# BallDetector6A.net
KiCad netlist of a schematic drawn in EAGLE
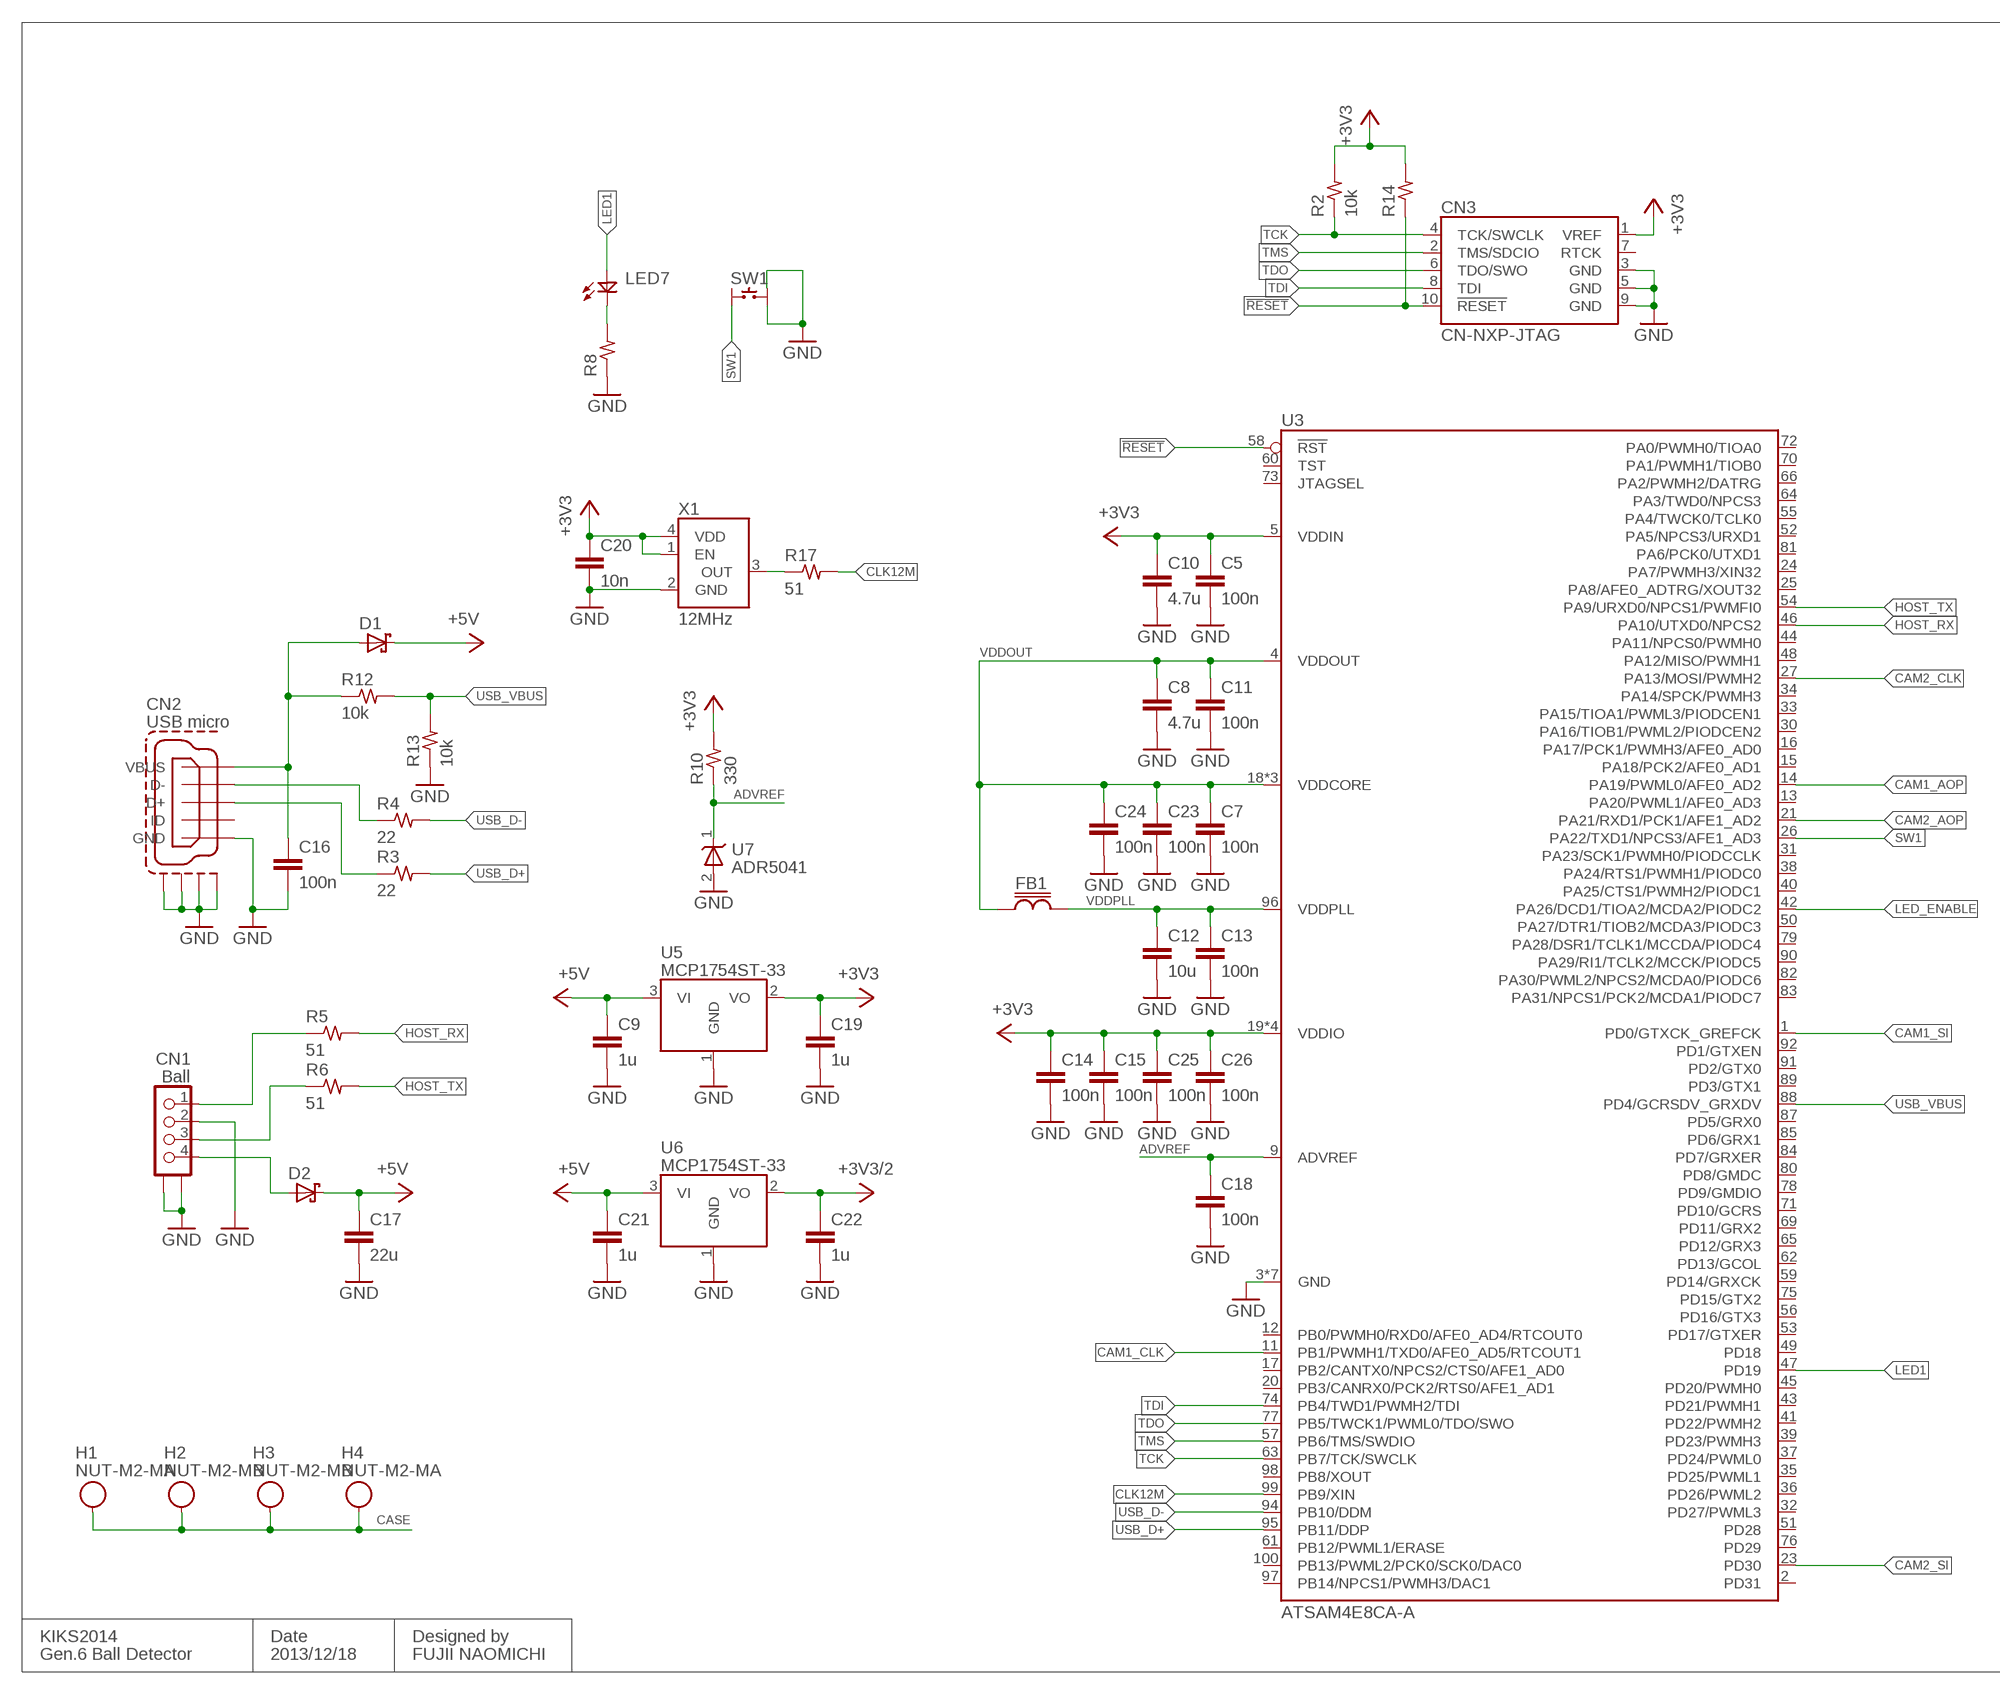
[diagram p0: schematic, sheet 1, part 1 of 2]
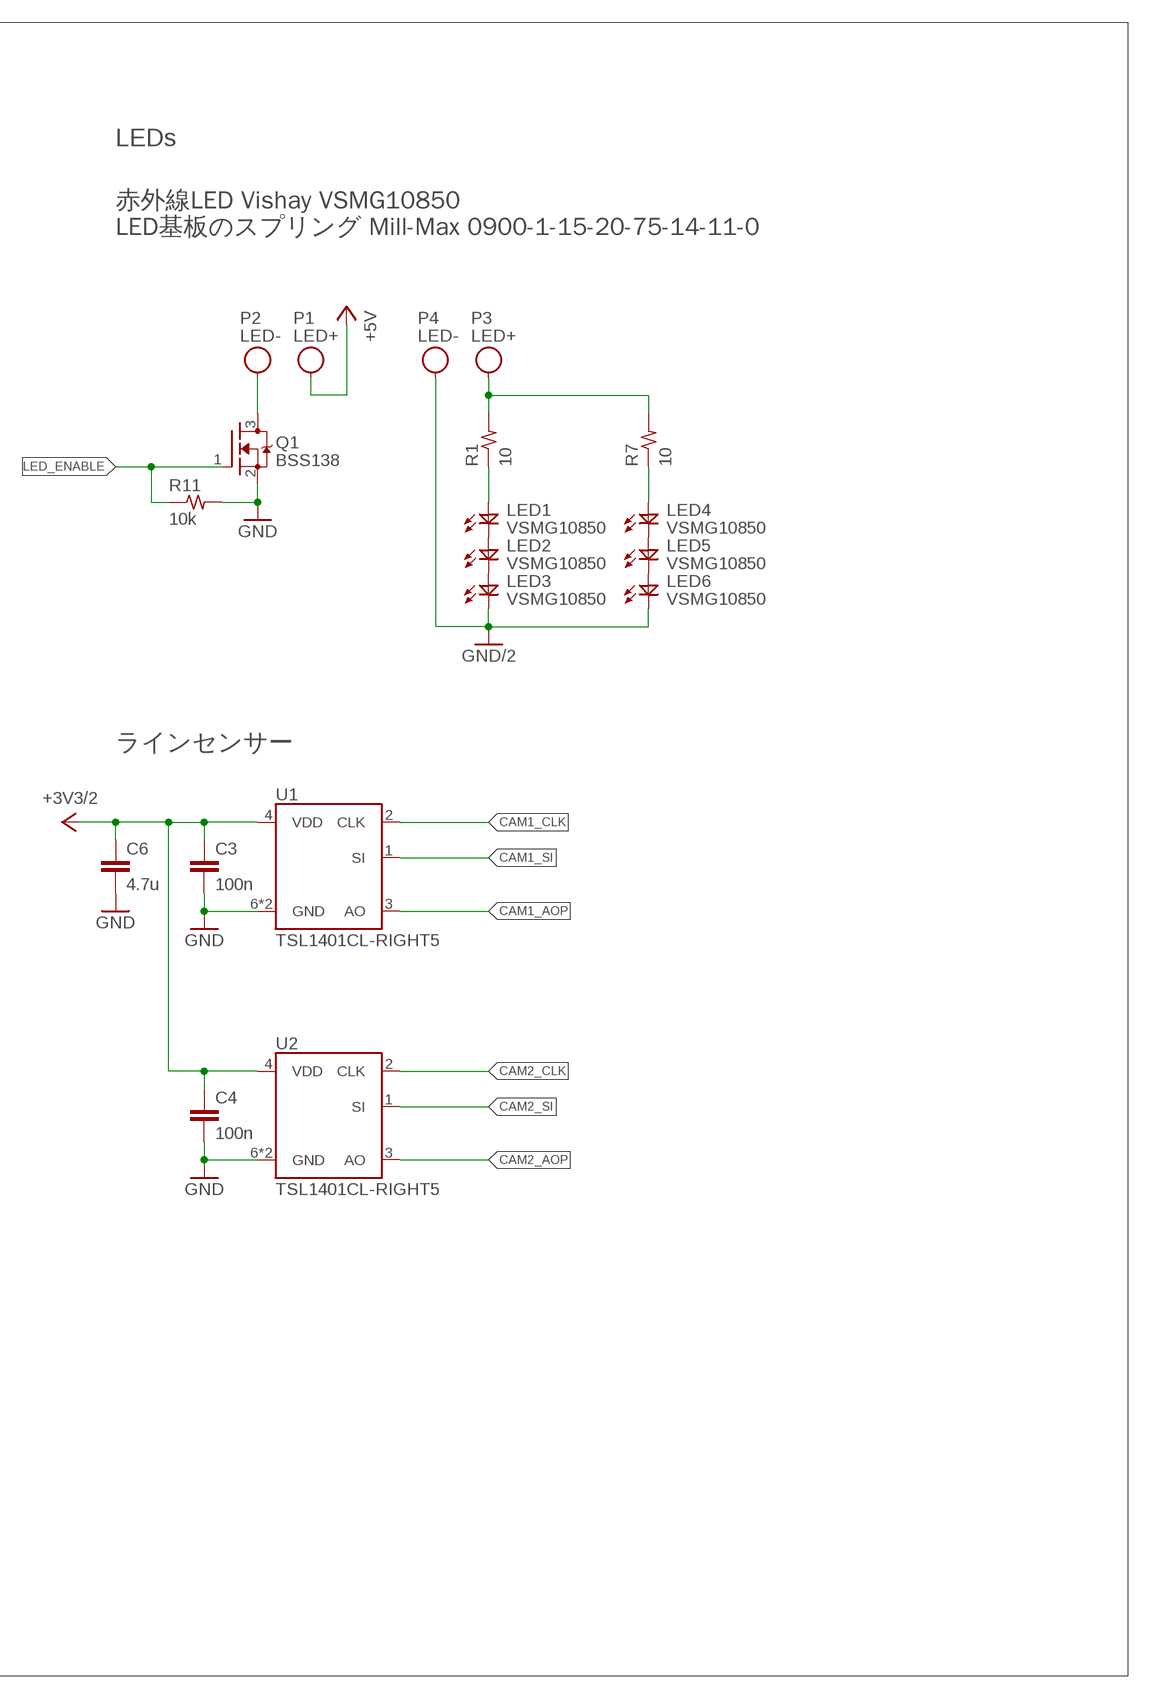
[diagram p1: schematic, sheet 1, part 2 of 2]

(export (version "E")
  (design (tool "Eeschema 10.0.6"))
  (components
    (comp (ref "C3")
      (value "100n")
      (footprint "eagle-import:1005")
      (libsource (lib "eagle-import") (part "C1005"))
    )
    (comp (ref "C4")
      (value "100n")
      (footprint "eagle-import:1005")
      (libsource (lib "eagle-import") (part "C1005"))
    )
    (comp (ref "C5")
      (value "100n")
      (footprint "eagle-import:1005")
      (libsource (lib "eagle-import") (part "C1005"))
    )
    (comp (ref "C6")
      (value "4.7u")
      (footprint "eagle-import:1608")
      (libsource (lib "eagle-import") (part "C1608"))
    )
    (comp (ref "C7")
      (value "100n")
      (footprint "eagle-import:1005")
      (libsource (lib "eagle-import") (part "C1005"))
    )
    (comp (ref "C8")
      (value "4.7u")
      (footprint "eagle-import:1608")
      (libsource (lib "eagle-import") (part "C1608"))
    )
    (comp (ref "C9")
      (value "1u")
      (footprint "eagle-import:1005")
      (libsource (lib "eagle-import") (part "C1005"))
    )
    (comp (ref "C10")
      (value "4.7u")
      (footprint "eagle-import:1608")
      (libsource (lib "eagle-import") (part "C1608"))
    )
    (comp (ref "C11")
      (value "100n")
      (footprint "eagle-import:1005")
      (libsource (lib "eagle-import") (part "C1005"))
    )
    (comp (ref "C12")
      (value "10u")
      (footprint "eagle-import:1005")
      (libsource (lib "eagle-import") (part "C1005"))
    )
    (comp (ref "C13")
      (value "100n")
      (footprint "eagle-import:1005")
      (libsource (lib "eagle-import") (part "C1005"))
    )
    (comp (ref "C14")
      (value "100n")
      (footprint "eagle-import:1005")
      (libsource (lib "eagle-import") (part "C1005"))
    )
    (comp (ref "C15")
      (value "100n")
      (footprint "eagle-import:1005")
      (libsource (lib "eagle-import") (part "C1005"))
    )
    (comp (ref "C16")
      (value "100n")
      (footprint "eagle-import:1005")
      (libsource (lib "eagle-import") (part "C1005"))
    )
    (comp (ref "C17")
      (value "22u")
      (footprint "eagle-import:2012")
      (libsource (lib "eagle-import") (part "C2012"))
    )
    (comp (ref "C18")
      (value "100n")
      (footprint "eagle-import:1005")
      (libsource (lib "eagle-import") (part "C1005"))
    )
    (comp (ref "C19")
      (value "1u")
      (footprint "eagle-import:1005")
      (libsource (lib "eagle-import") (part "C1005"))
    )
    (comp (ref "C20")
      (value "10n")
      (footprint "eagle-import:1005")
      (libsource (lib "eagle-import") (part "C1005"))
    )
    (comp (ref "C21")
      (value "1u")
      (footprint "eagle-import:1005")
      (libsource (lib "eagle-import") (part "C1005"))
    )
    (comp (ref "C22")
      (value "1u")
      (footprint "eagle-import:1005")
      (libsource (lib "eagle-import") (part "C1005"))
    )
    (comp (ref "C23")
      (value "100n")
      (footprint "eagle-import:1005")
      (libsource (lib "eagle-import") (part "C1005"))
    )
    (comp (ref "C24")
      (value "100n")
      (footprint "eagle-import:1005")
      (libsource (lib "eagle-import") (part "C1005"))
    )
    (comp (ref "C25")
      (value "100n")
      (footprint "eagle-import:1005")
      (libsource (lib "eagle-import") (part "C1005"))
    )
    (comp (ref "C26")
      (value "100n")
      (footprint "eagle-import:1005")
      (libsource (lib "eagle-import") (part "C1005"))
    )
    (comp (ref "CN1")
      (value "Ball")
      (footprint "eagle-import:53398-04")
      (libsource (lib "eagle-import") (part "53398-0471"))
    )
    (comp (ref "CN2")
      (value "USB micro")
      (footprint "eagle-import:ZX62-B-5PA")
      (libsource (lib "eagle-import") (part "ZX62-B-5PA"))
    )
    (comp (ref "CN3")
      (value "CN-NXP-JTAG")
      (footprint "eagle-import:PIN2X5-SMT1.27")
      (libsource (lib "eagle-import") (part "CN-NXP-JTAG"))
    )
    (comp (ref "D1")
      (value "SBD-SOD523")
      (footprint "eagle-import:SOD523")
      (libsource (lib "eagle-import") (part "SBD-SOD523"))
    )
    (comp (ref "D2")
      (value "SBD-SOD523")
      (footprint "eagle-import:SOD523")
      (libsource (lib "eagle-import") (part "SBD-SOD523"))
    )
    (comp (ref "FB1")
      (value "FB1608")
      (footprint "eagle-import:1608")
      (libsource (lib "eagle-import") (part "FB1608"))
    )
    (comp (ref "H1")
      (value "NUT-M2-MA")
      (footprint "eagle-import:NUT-M2-MA")
      (libsource (lib "eagle-import") (part "NUT-M2-MA"))
    )
    (comp (ref "H2")
      (value "NUT-M2-MB")
      (footprint "eagle-import:NUT-M2-MB")
      (libsource (lib "eagle-import") (part "NUT-M2-MB"))
    )
    (comp (ref "H3")
      (value "NUT-M2-MB")
      (footprint "eagle-import:NUT-M2-MB")
      (libsource (lib "eagle-import") (part "NUT-M2-MB"))
    )
    (comp (ref "H4")
      (value "NUT-M2-MA")
      (footprint "eagle-import:NUT-M2-MA")
      (libsource (lib "eagle-import") (part "NUT-M2-MA"))
    )
    (comp (ref "LED1")
      (value "VSMG10850")
      (footprint "eagle-import:3010")
      (libsource (lib "eagle-import") (part "VSMG10850"))
    )
    (comp (ref "LED2")
      (value "VSMG10850")
      (footprint "eagle-import:3010")
      (libsource (lib "eagle-import") (part "VSMG10850"))
    )
    (comp (ref "LED3")
      (value "VSMG10850")
      (footprint "eagle-import:3010")
      (libsource (lib "eagle-import") (part "VSMG10850"))
    )
    (comp (ref "LED4")
      (value "VSMG10850")
      (footprint "eagle-import:3010")
      (libsource (lib "eagle-import") (part "VSMG10850"))
    )
    (comp (ref "LED5")
      (value "VSMG10850")
      (footprint "eagle-import:3010")
      (libsource (lib "eagle-import") (part "VSMG10850"))
    )
    (comp (ref "LED6")
      (value "VSMG10850")
      (footprint "eagle-import:3010")
      (libsource (lib "eagle-import") (part "VSMG10850"))
    )
    (comp (ref "LED7")
      (value "LED1608")
      (footprint "eagle-import:1608")
      (libsource (lib "eagle-import") (part "LED1608"))
    )
    (comp (ref "P1")
      (value "LED+")
      (footprint "eagle-import:SPRING-72MIL")
      (libsource (lib "eagle-import") (part "SPRING-72MIL"))
    )
    (comp (ref "P2")
      (value "LED-")
      (footprint "eagle-import:SPRING-72MIL")
      (libsource (lib "eagle-import") (part "SPRING-72MIL"))
    )
    (comp (ref "P3")
      (value "LED+")
      (footprint "eagle-import:SPRING-72MIL")
      (libsource (lib "eagle-import") (part "SPRING-72MIL"))
    )
    (comp (ref "P4")
      (value "LED-")
      (footprint "eagle-import:SPRING-72MIL")
      (libsource (lib "eagle-import") (part "SPRING-72MIL"))
    )
    (comp (ref "Q1")
      (value "BSS138")
      (footprint "eagle-import:SOT23-3")
      (libsource (lib "eagle-import") (part "MOS-N-SOT23"))
    )
    (comp (ref "R1")
      (value "10")
      (footprint "eagle-import:1608")
      (libsource (lib "eagle-import") (part "R1608"))
    )
    (comp (ref "R2")
      (value "10k")
      (footprint "eagle-import:1005")
      (libsource (lib "eagle-import") (part "R1005"))
    )
    (comp (ref "R3")
      (value "22")
      (footprint "eagle-import:1005")
      (libsource (lib "eagle-import") (part "R1005"))
    )
    (comp (ref "R4")
      (value "22")
      (footprint "eagle-import:1005")
      (libsource (lib "eagle-import") (part "R1005"))
    )
    (comp (ref "R5")
      (value "51")
      (footprint "eagle-import:1005")
      (libsource (lib "eagle-import") (part "R1005"))
    )
    (comp (ref "R6")
      (value "51")
      (footprint "eagle-import:1005")
      (libsource (lib "eagle-import") (part "R1005"))
    )
    (comp (ref "R7")
      (value "10")
      (footprint "eagle-import:1608")
      (libsource (lib "eagle-import") (part "R1608"))
    )
    (comp (ref "R8")
      (value "R1005")
      (footprint "eagle-import:1005")
      (libsource (lib "eagle-import") (part "R1005"))
    )
    (comp (ref "R10")
      (value "330")
      (footprint "eagle-import:1005")
      (libsource (lib "eagle-import") (part "R1005"))
    )
    (comp (ref "R11")
      (value "10k")
      (footprint "eagle-import:1005")
      (libsource (lib "eagle-import") (part "R1005"))
    )
    (comp (ref "R12")
      (value "10k")
      (footprint "eagle-import:1005")
      (libsource (lib "eagle-import") (part "R1005"))
    )
    (comp (ref "R13")
      (value "10k")
      (footprint "eagle-import:1005")
      (libsource (lib "eagle-import") (part "R1005"))
    )
    (comp (ref "R14")
      (value "R1005")
      (footprint "eagle-import:1005")
      (libsource (lib "eagle-import") (part "R1005"))
    )
    (comp (ref "R17")
      (value "51")
      (footprint "eagle-import:1005")
      (libsource (lib "eagle-import") (part "R1005"))
    )
    (comp (ref "SW1")
      (value "SKRP")
      (footprint "eagle-import:SKRP")
      (libsource (lib "eagle-import") (part "SKRP"))
    )
    (comp (ref "U1")
      (value "TSL1401CL-RIGHT5")
      (footprint "eagle-import:TSL1401CL-RIGHT5")
      (libsource (lib "eagle-import") (part "TSL1401CL-RIGHT5"))
    )
    (comp (ref "U2")
      (value "TSL1401CL-RIGHT5")
      (footprint "eagle-import:TSL1401CL-RIGHT5")
      (libsource (lib "eagle-import") (part "TSL1401CL-RIGHT5"))
    )
    (comp (ref "U3")
      (value "ATSAM4E8CA-A")
      (footprint "eagle-import:QFP100-0.5")
      (libsource (lib "eagle-import") (part "ATSAM4ECA-?A8"))
    )
    (comp (ref "U5")
      (value "MCP1754ST-33")
      (footprint "eagle-import:SOT23-3")
      (libsource (lib "eagle-import") (part "MCP1754ST-33"))
    )
    (comp (ref "U6")
      (value "MCP1754ST-33")
      (footprint "eagle-import:SOT23-3")
      (libsource (lib "eagle-import") (part "MCP1754ST-33"))
    )
    (comp (ref "U7")
      (value "ADR5041")
      (footprint "eagle-import:SC70-3")
      (libsource (lib "eagle-import") (part "ADR5041"))
    )
    (comp (ref "X1")
      (value "12MHz")
      (footprint "eagle-import:OSC2520")
      (libsource (lib "eagle-import") (part "ASDMB"))
    )
  )
  (nets
    (net (code "1") (name "+3V3") (class "Default")
      (node (ref "C10") (pin "1") (pinfunction "1_1") (pintype "passive"))
      (node (ref "C14") (pin "1") (pinfunction "1_1") (pintype "passive"))
      (node (ref "C15") (pin "1") (pinfunction "1_1") (pintype "passive"))
      (node (ref "C19") (pin "1") (pinfunction "1_1") (pintype "passive"))
      (node (ref "C20") (pin "1") (pinfunction "1_1") (pintype "passive"))
      (node (ref "C25") (pin "1") (pinfunction "1_1") (pintype "passive"))
      (node (ref "C26") (pin "1") (pinfunction "1_1") (pintype "passive"))
      (node (ref "C5") (pin "1") (pinfunction "1_1") (pintype "passive"))
      (node (ref "CN3") (pin "1") (pinfunction "VREF_1") (pintype "passive"))
      (node (ref "R10") (pin "2") (pinfunction "2_2") (pintype "passive"))
      (node (ref "R14") (pin "2") (pinfunction "2_2") (pintype "passive"))
      (node (ref "R2") (pin "2") (pinfunction "2_2") (pintype "passive"))
      (node (ref "U3") (pin "19") (pinfunction "VDDIO_19") (pintype "bidirectional"))
      (node (ref "U3") (pin "28") (pinfunction "VDDIO_28") (pintype "bidirectional"))
      (node (ref "U3") (pin "5") (pinfunction "VDDIN_5") (pintype "bidirectional"))
      (node (ref "U3") (pin "68") (pinfunction "VDDIO_68") (pintype "bidirectional"))
      (node (ref "U3") (pin "93") (pinfunction "VDDIO_93") (pintype "bidirectional"))
      (node (ref "U5") (pin "2") (pinfunction "VO_2") (pintype "bidirectional"))
      (node (ref "X1") (pin "1") (pinfunction "EN_1") (pintype "bidirectional"))
      (node (ref "X1") (pin "4") (pinfunction "VDD_4") (pintype "bidirectional"))
    )
    (net (code "2") (name "+3V3{slash}2") (class "Default")
      (node (ref "C22") (pin "1") (pinfunction "1_1") (pintype "passive"))
      (node (ref "C3") (pin "1") (pinfunction "1_1") (pintype "passive"))
      (node (ref "C4") (pin "1") (pinfunction "1_1") (pintype "passive"))
      (node (ref "C6") (pin "1") (pinfunction "1_1") (pintype "passive"))
      (node (ref "U1") (pin "4") (pinfunction "VDD_4") (pintype "bidirectional"))
      (node (ref "U2") (pin "4") (pinfunction "VDD_4") (pintype "bidirectional"))
      (node (ref "U6") (pin "2") (pinfunction "VO_2") (pintype "bidirectional"))
    )
    (net (code "3") (name "+5V") (class "Default")
      (node (ref "C17") (pin "1") (pinfunction "1_1") (pintype "passive"))
      (node (ref "C21") (pin "1") (pinfunction "1_1") (pintype "passive"))
      (node (ref "C9") (pin "1") (pinfunction "1_1") (pintype "passive"))
      (node (ref "D1") (pin "K") (pinfunction "K_K") (pintype "passive"))
      (node (ref "D2") (pin "K") (pinfunction "K_K") (pintype "passive"))
      (node (ref "P1") (pin "1") (pinfunction "1_1") (pintype "passive"))
      (node (ref "U5") (pin "3") (pinfunction "VI_3") (pintype "bidirectional"))
      (node (ref "U6") (pin "3") (pinfunction "VI_3") (pintype "bidirectional"))
    )
    (net (code "4") (name "/ADVREF") (class "Default")
      (node (ref "C18") (pin "1") (pinfunction "1_1") (pintype "passive"))
      (node (ref "R10") (pin "1") (pinfunction "1_1") (pintype "passive"))
      (node (ref "U3") (pin "9") (pinfunction "ADVREF_9") (pintype "bidirectional"))
      (node (ref "U7") (pin "1") (pinfunction "K_1") (pintype "passive"))
    )
    (net (code "5") (name "/CASE") (class "Default")
      (node (ref "H1") (pin "1") (pinfunction "1_1") (pintype "passive"))
      (node (ref "H1") (pin "2") (pinfunction "1_2") (pintype "passive"))
      (node (ref "H2") (pin "1") (pinfunction "1_1") (pintype "passive"))
      (node (ref "H2") (pin "2") (pinfunction "1_2") (pintype "passive"))
      (node (ref "H3") (pin "1") (pinfunction "1_1") (pintype "passive"))
      (node (ref "H3") (pin "2") (pinfunction "1_2") (pintype "passive"))
      (node (ref "H4") (pin "1") (pinfunction "1_1") (pintype "passive"))
      (node (ref "H4") (pin "2") (pinfunction "1_2") (pintype "passive"))
    )
    (net (code "6") (name "/VDDOUT") (class "Default")
      (node (ref "C11") (pin "1") (pinfunction "1_1") (pintype "passive"))
      (node (ref "C23") (pin "1") (pinfunction "1_1") (pintype "passive"))
      (node (ref "C24") (pin "1") (pinfunction "1_1") (pintype "passive"))
      (node (ref "C7") (pin "1") (pinfunction "1_1") (pintype "passive"))
      (node (ref "C8") (pin "1") (pinfunction "1_1") (pintype "passive"))
      (node (ref "FB1") (pin "1") (pinfunction "1_1") (pintype "passive"))
      (node (ref "U3") (pin "18") (pinfunction "VDDCORE_18") (pintype "bidirectional"))
      (node (ref "U3") (pin "22") (pinfunction "VDDCORE_22") (pintype "bidirectional"))
      (node (ref "U3") (pin "4") (pinfunction "VDDOUT_4") (pintype "bidirectional"))
      (node (ref "U3") (pin "86") (pinfunction "VDDCORE_86") (pintype "bidirectional"))
    )
    (net (code "7") (name "/VDDPLL") (class "Default")
      (node (ref "C12") (pin "1") (pinfunction "1_1") (pintype "passive"))
      (node (ref "C13") (pin "1") (pinfunction "1_1") (pintype "passive"))
      (node (ref "FB1") (pin "2") (pinfunction "2_2") (pintype "passive"))
      (node (ref "U3") (pin "96") (pinfunction "VDDPLL_96") (pintype "bidirectional"))
    )
    (net (code "8") (name "/~{RESET}") (class "Default")
      (node (ref "CN3") (pin "10") (pinfunction "~{RESET}_10") (pintype "passive"))
      (node (ref "R14") (pin "1") (pinfunction "1_1") (pintype "passive"))
      (node (ref "U3") (pin "58") (pinfunction "~{RST}_58") (pintype "bidirectional"))
    )
    (net (code "9") (name "CAM1_AOP") (class "Default")
      (node (ref "U1") (pin "3") (pinfunction "AO_3") (pintype "bidirectional"))
      (node (ref "U3") (pin "14") (pinfunction "PA19/PWML0/AFE0_AD2_14") (pintype "bidirectional"))
    )
    (net (code "10") (name "CAM1_CLK") (class "Default")
      (node (ref "U1") (pin "2") (pinfunction "CLK_2") (pintype "bidirectional"))
      (node (ref "U3") (pin "11") (pinfunction "PB1/PWMH1/TXD0/AFE0_AD5/RTCOUT1_11") (pintype "bidirectional"))
    )
    (net (code "11") (name "CAM1_SI") (class "Default")
      (node (ref "U1") (pin "1") (pinfunction "SI_1") (pintype "bidirectional"))
      (node (ref "U3") (pin "1") (pinfunction "PD0/GTXCK_GREFCK_1") (pintype "bidirectional"))
    )
    (net (code "12") (name "CAM2_AOP") (class "Default")
      (node (ref "U2") (pin "3") (pinfunction "AO_3") (pintype "bidirectional"))
      (node (ref "U3") (pin "21") (pinfunction "PA21/RXD1/PCK1/AFE1_AD2_21") (pintype "bidirectional"))
    )
    (net (code "13") (name "CAM2_CLK") (class "Default")
      (node (ref "U2") (pin "2") (pinfunction "CLK_2") (pintype "bidirectional"))
      (node (ref "U3") (pin "27") (pinfunction "PA13/MOSI/PWMH2_27") (pintype "bidirectional"))
    )
    (net (code "14") (name "CAM2_SI") (class "Default")
      (node (ref "U2") (pin "1") (pinfunction "SI_1") (pintype "bidirectional"))
      (node (ref "U3") (pin "23") (pinfunction "PD30_23") (pintype "bidirectional"))
    )
    (net (code "15") (name "CLK12M") (class "Default")
      (node (ref "R17") (pin "2") (pinfunction "2_2") (pintype "passive"))
      (node (ref "U3") (pin "99") (pinfunction "PB9/XIN_99") (pintype "bidirectional"))
    )
    (net (code "16") (name "GND") (class "Default")
      (node (ref "C10") (pin "2") (pinfunction "2_2") (pintype "passive"))
      (node (ref "C11") (pin "2") (pinfunction "2_2") (pintype "passive"))
      (node (ref "C12") (pin "2") (pinfunction "2_2") (pintype "passive"))
      (node (ref "C13") (pin "2") (pinfunction "2_2") (pintype "passive"))
      (node (ref "C14") (pin "2") (pinfunction "2_2") (pintype "passive"))
      (node (ref "C15") (pin "2") (pinfunction "2_2") (pintype "passive"))
      (node (ref "C16") (pin "2") (pinfunction "2_2") (pintype "passive"))
      (node (ref "C17") (pin "2") (pinfunction "2_2") (pintype "passive"))
      (node (ref "C18") (pin "2") (pinfunction "2_2") (pintype "passive"))
      (node (ref "C19") (pin "2") (pinfunction "2_2") (pintype "passive"))
      (node (ref "C20") (pin "2") (pinfunction "2_2") (pintype "passive"))
      (node (ref "C21") (pin "2") (pinfunction "2_2") (pintype "passive"))
      (node (ref "C22") (pin "2") (pinfunction "2_2") (pintype "passive"))
      (node (ref "C23") (pin "2") (pinfunction "2_2") (pintype "passive"))
      (node (ref "C24") (pin "2") (pinfunction "2_2") (pintype "passive"))
      (node (ref "C25") (pin "2") (pinfunction "2_2") (pintype "passive"))
      (node (ref "C26") (pin "2") (pinfunction "2_2") (pintype "passive"))
      (node (ref "C3") (pin "2") (pinfunction "2_2") (pintype "passive"))
      (node (ref "C4") (pin "2") (pinfunction "2_2") (pintype "passive"))
      (node (ref "C5") (pin "2") (pinfunction "2_2") (pintype "passive"))
      (node (ref "C6") (pin "2") (pinfunction "2_2") (pintype "passive"))
      (node (ref "C7") (pin "2") (pinfunction "2_2") (pintype "passive"))
      (node (ref "C8") (pin "2") (pinfunction "2_2") (pintype "passive"))
      (node (ref "C9") (pin "2") (pinfunction "2_2") (pintype "passive"))
      (node (ref "CN1") (pin "2") (pinfunction "2_2") (pintype "passive"))
      (node (ref "CN1") (pin "S1") (pinfunction "S1_S1") (pintype "passive"))
      (node (ref "CN1") (pin "S2") (pinfunction "S2_S2") (pintype "passive"))
      (node (ref "CN2") (pin "5") (pinfunction "GND_5") (pintype "passive"))
      (node (ref "CN2") (pin "S1") (pinfunction "S1_S1") (pintype "passive"))
      (node (ref "CN2") (pin "S2") (pinfunction "S2_S2") (pintype "passive"))
      (node (ref "CN2") (pin "S3") (pinfunction "S3_S3") (pintype "passive"))
      (node (ref "CN2") (pin "S4") (pinfunction "S4_S4") (pintype "passive"))
      (node (ref "CN3") (pin "3") (pinfunction "GND_3") (pintype "passive"))
      (node (ref "CN3") (pin "5") (pinfunction "GND_5") (pintype "passive"))
      (node (ref "CN3") (pin "9") (pinfunction "GND_9") (pintype "passive"))
      (node (ref "Q1") (pin "2") (pinfunction "S_2") (pintype "passive"))
      (node (ref "R11") (pin "2") (pinfunction "2_2") (pintype "passive"))
      (node (ref "R13") (pin "1") (pinfunction "1_1") (pintype "passive"))
      (node (ref "R8") (pin "1") (pinfunction "1_1") (pintype "passive"))
      (node (ref "SW1") (pin "B1") (pinfunction "B1_B1") (pintype "passive"))
      (node (ref "SW1") (pin "B2") (pinfunction "B2_B2") (pintype "passive"))
      (node (ref "U1") (pin "6") (pinfunction "GND_6") (pintype "bidirectional"))
      (node (ref "U1") (pin "7") (pinfunction "GND_7") (pintype "bidirectional"))
      (node (ref "U2") (pin "6") (pinfunction "GND_6") (pintype "bidirectional"))
      (node (ref "U2") (pin "7") (pinfunction "GND_7") (pintype "bidirectional"))
      (node (ref "U3") (pin "10") (pinfunction "GND_10") (pintype "bidirectional"))
      (node (ref "U3") (pin "29") (pinfunction "GND_29") (pintype "bidirectional"))
      (node (ref "U3") (pin "3") (pinfunction "GND_3") (pintype "bidirectional"))
      (node (ref "U3") (pin "6") (pinfunction "GND_6") (pintype "bidirectional"))
      (node (ref "U3") (pin "67") (pinfunction "GND_67") (pintype "bidirectional"))
      (node (ref "U3") (pin "7") (pinfunction "GND_7") (pintype "bidirectional"))
      (node (ref "U3") (pin "8") (pinfunction "GND_8") (pintype "bidirectional"))
      (node (ref "U5") (pin "1") (pinfunction "GND_1") (pintype "bidirectional"))
      (node (ref "U6") (pin "1") (pinfunction "GND_1") (pintype "bidirectional"))
      (node (ref "U7") (pin "2") (pinfunction "A_2") (pintype "passive"))
      (node (ref "X1") (pin "2") (pinfunction "GND_2") (pintype "bidirectional"))
    )
    (net (code "17") (name "GND{slash}2") (class "Default")
      (node (ref "LED3") (pin "K") (pinfunction "K_K") (pintype "passive"))
      (node (ref "LED6") (pin "K") (pinfunction "K_K") (pintype "passive"))
      (node (ref "P4") (pin "1") (pinfunction "1_1") (pintype "passive"))
    )
    (net (code "18") (name "HOST_RX") (class "Default")
      (node (ref "R5") (pin "2") (pinfunction "2_2") (pintype "passive"))
      (node (ref "U3") (pin "46") (pinfunction "PA10/UTXD0/NPCS2_46") (pintype "bidirectional"))
    )
    (net (code "19") (name "HOST_TX") (class "Default")
      (node (ref "R6") (pin "2") (pinfunction "2_2") (pintype "passive"))
      (node (ref "U3") (pin "54") (pinfunction "PA9/URXD0/NPCS1/PWMFI0_54") (pintype "bidirectional"))
    )
    (net (code "20") (name "LED1") (class "Default")
      (node (ref "LED7") (pin "A") (pinfunction "A_A") (pintype "passive"))
      (node (ref "U3") (pin "47") (pinfunction "PD19_47") (pintype "bidirectional"))
    )
    (net (code "21") (name "LED_ENABLE") (class "Default")
      (node (ref "Q1") (pin "1") (pinfunction "G_1") (pintype "passive"))
      (node (ref "R11") (pin "1") (pinfunction "1_1") (pintype "passive"))
      (node (ref "U3") (pin "42") (pinfunction "PA26/DCD1/TIOA2/MCDA2/PIODC2_42") (pintype "bidirectional"))
    )
    (net (code "22") (name "Net-(CN1-Pad1)") (class "Default")
      (node (ref "CN1") (pin "1") (pinfunction "1_1") (pintype "passive"))
      (node (ref "R5") (pin "1") (pinfunction "1_1") (pintype "passive"))
    )
    (net (code "23") (name "Net-(CN1-Pad3)") (class "Default")
      (node (ref "CN1") (pin "3") (pinfunction "3_3") (pintype "passive"))
      (node (ref "R6") (pin "1") (pinfunction "1_1") (pintype "passive"))
    )
    (net (code "24") (name "Net-(CN1-Pad4)") (class "Default")
      (node (ref "CN1") (pin "4") (pinfunction "4_4") (pintype "passive"))
      (node (ref "D2") (pin "A") (pinfunction "A_A") (pintype "passive"))
    )
    (net (code "25") (name "Net-(CN2-D+)") (class "Default")
      (node (ref "CN2") (pin "3") (pinfunction "D+_3") (pintype "passive"))
      (node (ref "R3") (pin "1") (pinfunction "1_1") (pintype "passive"))
    )
    (net (code "26") (name "Net-(CN2-D-)") (class "Default")
      (node (ref "CN2") (pin "2") (pinfunction "D-_2") (pintype "passive"))
      (node (ref "R4") (pin "1") (pinfunction "1_1") (pintype "passive"))
    )
    (net (code "27") (name "Net-(CN2-VBUS)") (class "Default")
      (node (ref "C16") (pin "1") (pinfunction "1_1") (pintype "passive"))
      (node (ref "CN2") (pin "1") (pinfunction "VBUS_1") (pintype "passive"))
      (node (ref "D1") (pin "A") (pinfunction "A_A") (pintype "passive"))
      (node (ref "R12") (pin "1") (pinfunction "1_1") (pintype "passive"))
    )
    (net (code "28") (name "Net-(LED1-PadA)") (class "Default")
      (node (ref "LED1") (pin "A") (pinfunction "A_A") (pintype "passive"))
      (node (ref "R1") (pin "1") (pinfunction "1_1") (pintype "passive"))
    )
    (net (code "29") (name "Net-(LED1-PadK)") (class "Default")
      (node (ref "LED1") (pin "K") (pinfunction "K_K") (pintype "passive"))
      (node (ref "LED2") (pin "A") (pinfunction "A_A") (pintype "passive"))
    )
    (net (code "30") (name "Net-(LED2-PadK)") (class "Default")
      (node (ref "LED2") (pin "K") (pinfunction "K_K") (pintype "passive"))
      (node (ref "LED3") (pin "A") (pinfunction "A_A") (pintype "passive"))
    )
    (net (code "31") (name "Net-(LED4-PadA)") (class "Default")
      (node (ref "LED4") (pin "A") (pinfunction "A_A") (pintype "passive"))
      (node (ref "R7") (pin "1") (pinfunction "1_1") (pintype "passive"))
    )
    (net (code "32") (name "Net-(LED4-PadK)") (class "Default")
      (node (ref "LED4") (pin "K") (pinfunction "K_K") (pintype "passive"))
      (node (ref "LED5") (pin "A") (pinfunction "A_A") (pintype "passive"))
    )
    (net (code "33") (name "Net-(LED5-PadK)") (class "Default")
      (node (ref "LED5") (pin "K") (pinfunction "K_K") (pintype "passive"))
      (node (ref "LED6") (pin "A") (pinfunction "A_A") (pintype "passive"))
    )
    (net (code "34") (name "Net-(LED7-PadK)") (class "Default")
      (node (ref "LED7") (pin "K") (pinfunction "K_K") (pintype "passive"))
      (node (ref "R8") (pin "2") (pinfunction "2_2") (pintype "passive"))
    )
    (net (code "35") (name "Net-(P3-Pad1)") (class "Default")
      (node (ref "P3") (pin "1") (pinfunction "1_1") (pintype "passive"))
      (node (ref "R1") (pin "2") (pinfunction "2_2") (pintype "passive"))
      (node (ref "R7") (pin "2") (pinfunction "2_2") (pintype "passive"))
    )
    (net (code "36") (name "Net-(Q1-D)") (class "Default")
      (node (ref "P2") (pin "1") (pinfunction "1_1") (pintype "passive"))
      (node (ref "Q1") (pin "3") (pinfunction "D_3") (pintype "passive"))
    )
    (net (code "37") (name "Net-(X1-OUT)") (class "Default")
      (node (ref "R17") (pin "1") (pinfunction "1_1") (pintype "passive"))
      (node (ref "X1") (pin "3") (pinfunction "OUT_3") (pintype "bidirectional"))
    )
    (net (code "38") (name "SW1") (class "Default")
      (node (ref "SW1") (pin "A2") (pinfunction "A2_A2") (pintype "passive"))
      (node (ref "U3") (pin "26") (pinfunction "PA22/TXD1/NPCS3/AFE1_AD3_26") (pintype "bidirectional"))
    )
    (net (code "39") (name "TCK") (class "Default")
      (node (ref "CN3") (pin "4") (pinfunction "TCK/SWCLK_4") (pintype "passive"))
      (node (ref "R2") (pin "1") (pinfunction "1_1") (pintype "passive"))
      (node (ref "U3") (pin "63") (pinfunction "PB7/TCK/SWCLK_63") (pintype "bidirectional"))
    )
    (net (code "40") (name "TDI") (class "Default")
      (node (ref "CN3") (pin "8") (pinfunction "TDI_8") (pintype "passive"))
      (node (ref "U3") (pin "74") (pinfunction "PB4/TWD1/PWMH2/TDI_74") (pintype "bidirectional"))
    )
    (net (code "41") (name "TDO") (class "Default")
      (node (ref "CN3") (pin "6") (pinfunction "TDO/SWO_6") (pintype "passive"))
      (node (ref "U3") (pin "77") (pinfunction "PB5/TWCK1/PWML0/TDO/SWO_77") (pintype "bidirectional"))
    )
    (net (code "42") (name "TMS") (class "Default")
      (node (ref "CN3") (pin "2") (pinfunction "TMS/SDCIO_2") (pintype "passive"))
      (node (ref "U3") (pin "57") (pinfunction "PB6/TMS/SWDIO_57") (pintype "bidirectional"))
    )
    (net (code "43") (name "USB_D+") (class "Default")
      (node (ref "R3") (pin "2") (pinfunction "2_2") (pintype "passive"))
      (node (ref "U3") (pin "95") (pinfunction "PB11/DDP_95") (pintype "bidirectional"))
    )
    (net (code "44") (name "USB_D-") (class "Default")
      (node (ref "R4") (pin "2") (pinfunction "2_2") (pintype "passive"))
      (node (ref "U3") (pin "94") (pinfunction "PB10/DDM_94") (pintype "bidirectional"))
    )
    (net (code "45") (name "USB_VBUS") (class "Default")
      (node (ref "R12") (pin "2") (pinfunction "2_2") (pintype "passive"))
      (node (ref "R13") (pin "2") (pinfunction "2_2") (pintype "passive"))
      (node (ref "U3") (pin "88") (pinfunction "PD4/GCRSDV_GRXDV_88") (pintype "bidirectional"))
    )
    (net (code "46") (name "unconnected-(CN2-ID-Pad4)") (class "Default")
      (node (ref "CN2") (pin "4") (pinfunction "ID_4") (pintype "passive"))
    )
    (net (code "47") (name "unconnected-(CN3-RTCK-Pad7)") (class "Default")
      (node (ref "CN3") (pin "7") (pinfunction "RTCK_7") (pintype "passive"))
    )
    (net (code "48") (name "unconnected-(SW1-PadA1)") (class "Default")
      (node (ref "SW1") (pin "A1") (pinfunction "A1_A1") (pintype "passive"))
    )
    (net (code "49") (name "unconnected-(U3-JTAGSEL-Pad73)") (class "Default")
      (node (ref "U3") (pin "73") (pinfunction "JTAGSEL_73") (pintype "bidirectional"))
    )
    (net (code "50") (name "unconnected-(U3-PA0{slash}PWMH0{slash}TIOA0-Pad72)") (class "Default")
      (node (ref "U3") (pin "72") (pinfunction "PA0/PWMH0/TIOA0_72") (pintype "bidirectional"))
    )
    (net (code "51") (name "unconnected-(U3-PA1{slash}PWMH1{slash}TIOB0-Pad70)") (class "Default")
      (node (ref "U3") (pin "70") (pinfunction "PA1/PWMH1/TIOB0_70") (pintype "bidirectional"))
    )
    (net (code "52") (name "unconnected-(U3-PA2{slash}PWMH2{slash}DATRG-Pad66)") (class "Default")
      (node (ref "U3") (pin "66") (pinfunction "PA2/PWMH2/DATRG_66") (pintype "bidirectional"))
    )
    (net (code "53") (name "unconnected-(U3-PA3{slash}TWD0{slash}NPCS3-Pad64)") (class "Default")
      (node (ref "U3") (pin "64") (pinfunction "PA3/TWD0/NPCS3_64") (pintype "bidirectional"))
    )
    (net (code "54") (name "unconnected-(U3-PA4{slash}TWCK0{slash}TCLK0-Pad55)") (class "Default")
      (node (ref "U3") (pin "55") (pinfunction "PA4/TWCK0/TCLK0_55") (pintype "bidirectional"))
    )
    (net (code "55") (name "unconnected-(U3-PA5{slash}NPCS3{slash}URXD1-Pad52)") (class "Default")
      (node (ref "U3") (pin "52") (pinfunction "PA5/NPCS3/URXD1_52") (pintype "bidirectional"))
    )
    (net (code "56") (name "unconnected-(U3-PA6{slash}PCK0{slash}UTXD1-Pad81)") (class "Default")
      (node (ref "U3") (pin "81") (pinfunction "PA6/PCK0/UTXD1_81") (pintype "bidirectional"))
    )
    (net (code "57") (name "unconnected-(U3-PA7{slash}PWMH3{slash}XIN32-Pad24)") (class "Default")
      (node (ref "U3") (pin "24") (pinfunction "PA7/PWMH3/XIN32_24") (pintype "bidirectional"))
    )
    (net (code "58") (name "unconnected-(U3-PA8{slash}AFE0_ADTRG{slash}XOUT32-Pad25)") (class "Default")
      (node (ref "U3") (pin "25") (pinfunction "PA8/AFE0_ADTRG/XOUT32_25") (pintype "bidirectional"))
    )
    (net (code "59") (name "unconnected-(U3-PA11{slash}NPCS0{slash}PWMH0-Pad44)") (class "Default")
      (node (ref "U3") (pin "44") (pinfunction "PA11/NPCS0/PWMH0_44") (pintype "bidirectional"))
    )
    (net (code "60") (name "unconnected-(U3-PA12{slash}MISO{slash}PWMH1-Pad48)") (class "Default")
      (node (ref "U3") (pin "48") (pinfunction "PA12/MISO/PWMH1_48") (pintype "bidirectional"))
    )
    (net (code "61") (name "unconnected-(U3-PA14{slash}SPCK{slash}PWMH3-Pad34)") (class "Default")
      (node (ref "U3") (pin "34") (pinfunction "PA14/SPCK/PWMH3_34") (pintype "bidirectional"))
    )
    (net (code "62") (name "unconnected-(U3-PA15{slash}TIOA1{slash}PWML3{slash}PIODCEN1-Pad33)") (class "Default")
      (node (ref "U3") (pin "33") (pinfunction "PA15/TIOA1/PWML3/PIODCEN1_33") (pintype "bidirectional"))
    )
    (net (code "63") (name "unconnected-(U3-PA16{slash}TIOB1{slash}PWML2{slash}PIODCEN2-Pad30)") (class "Default")
      (node (ref "U3") (pin "30") (pinfunction "PA16/TIOB1/PWML2/PIODCEN2_30") (pintype "bidirectional"))
    )
    (net (code "64") (name "unconnected-(U3-PA17{slash}PCK1{slash}PWMH3{slash}AFE0_AD0-Pad16)") (class "Default")
      (node (ref "U3") (pin "16") (pinfunction "PA17/PCK1/PWMH3/AFE0_AD0_16") (pintype "bidirectional"))
    )
    (net (code "65") (name "unconnected-(U3-PA18{slash}PCK2{slash}AFE0_AD1-Pad15)") (class "Default")
      (node (ref "U3") (pin "15") (pinfunction "PA18/PCK2/AFE0_AD1_15") (pintype "bidirectional"))
    )
    (net (code "66") (name "unconnected-(U3-PA20{slash}PWML1{slash}AFE0_AD3-Pad13)") (class "Default")
      (node (ref "U3") (pin "13") (pinfunction "PA20/PWML1/AFE0_AD3_13") (pintype "bidirectional"))
    )
    (net (code "67") (name "unconnected-(U3-PA23{slash}SCK1{slash}PWMH0{slash}PIODCCLK-Pad31)") (class "Default")
      (node (ref "U3") (pin "31") (pinfunction "PA23/SCK1/PWMH0/PIODCCLK_31") (pintype "bidirectional"))
    )
    (net (code "68") (name "unconnected-(U3-PA24{slash}RTS1{slash}PWMH1{slash}PIODC0-Pad38)") (class "Default")
      (node (ref "U3") (pin "38") (pinfunction "PA24/RTS1/PWMH1/PIODC0_38") (pintype "bidirectional"))
    )
    (net (code "69") (name "unconnected-(U3-PA25{slash}CTS1{slash}PWMH2{slash}PIODC1-Pad40)") (class "Default")
      (node (ref "U3") (pin "40") (pinfunction "PA25/CTS1/PWMH2/PIODC1_40") (pintype "bidirectional"))
    )
    (net (code "70") (name "unconnected-(U3-PA27{slash}DTR1{slash}TIOB2{slash}MCDA3{slash}PIODC3-Pad50)") (class "Default")
      (node (ref "U3") (pin "50") (pinfunction "PA27/DTR1/TIOB2/MCDA3/PIODC3_50") (pintype "bidirectional"))
    )
    (net (code "71") (name "unconnected-(U3-PA28{slash}DSR1{slash}TCLK1{slash}MCCDA{slash}PIODC4-Pad79)") (class "Default")
      (node (ref "U3") (pin "79") (pinfunction "PA28/DSR1/TCLK1/MCCDA/PIODC4_79") (pintype "bidirectional"))
    )
    (net (code "72") (name "unconnected-(U3-PA29{slash}RI1{slash}TCLK2{slash}MCCK{slash}PIODC5-Pad90)") (class "Default")
      (node (ref "U3") (pin "90") (pinfunction "PA29/RI1/TCLK2/MCCK/PIODC5_90") (pintype "bidirectional"))
    )
    (net (code "73") (name "unconnected-(U3-PA30{slash}PWML2{slash}NPCS2{slash}MCDA0{slash}PIODC6-Pad82)") (class "Default")
      (node (ref "U3") (pin "82") (pinfunction "PA30/PWML2/NPCS2/MCDA0/PIODC6_82") (pintype "bidirectional"))
    )
    (net (code "74") (name "unconnected-(U3-PA31{slash}NPCS1{slash}PCK2{slash}MCDA1{slash}PIODC7-Pad83)") (class "Default")
      (node (ref "U3") (pin "83") (pinfunction "PA31/NPCS1/PCK2/MCDA1/PIODC7_83") (pintype "bidirectional"))
    )
    (net (code "75") (name "unconnected-(U3-PB0{slash}PWMH0{slash}RXD0{slash}AFE0_AD4{slash}RTCOUT0-Pad12)") (class "Default")
      (node (ref "U3") (pin "12") (pinfunction "PB0/PWMH0/RXD0/AFE0_AD4/RTCOUT0_12") (pintype "bidirectional"))
    )
    (net (code "76") (name "unconnected-(U3-PB2{slash}CANTX0{slash}NPCS2{slash}CTS0{slash}AFE1_AD0-Pad17)") (class "Default")
      (node (ref "U3") (pin "17") (pinfunction "PB2/CANTX0/NPCS2/CTS0/AFE1_AD0_17") (pintype "bidirectional"))
    )
    (net (code "77") (name "unconnected-(U3-PB3{slash}CANRX0{slash}PCK2{slash}RTS0{slash}AFE1_AD1-Pad20)") (class "Default")
      (node (ref "U3") (pin "20") (pinfunction "PB3/CANRX0/PCK2/RTS0/AFE1_AD1_20") (pintype "bidirectional"))
    )
    (net (code "78") (name "unconnected-(U3-PB8{slash}XOUT-Pad98)") (class "Default")
      (node (ref "U3") (pin "98") (pinfunction "PB8/XOUT_98") (pintype "bidirectional"))
    )
    (net (code "79") (name "unconnected-(U3-PB12{slash}PWML1{slash}ERASE-Pad61)") (class "Default")
      (node (ref "U3") (pin "61") (pinfunction "PB12/PWML1/ERASE_61") (pintype "bidirectional"))
    )
    (net (code "80") (name "unconnected-(U3-PB13{slash}PWML2{slash}PCK0{slash}SCK0{slash}DAC0-Pad100)") (class "Default")
      (node (ref "U3") (pin "100") (pinfunction "PB13/PWML2/PCK0/SCK0/DAC0_100") (pintype "bidirectional"))
    )
    (net (code "81") (name "unconnected-(U3-PB14{slash}NPCS1{slash}PWMH3{slash}DAC1-Pad97)") (class "Default")
      (node (ref "U3") (pin "97") (pinfunction "PB14/NPCS1/PWMH3/DAC1_97") (pintype "bidirectional"))
    )
    (net (code "82") (name "unconnected-(U3-PD1{slash}GTXEN-Pad92)") (class "Default")
      (node (ref "U3") (pin "92") (pinfunction "PD1/GTXEN_92") (pintype "bidirectional"))
    )
    (net (code "83") (name "unconnected-(U3-PD2{slash}GTX0-Pad91)") (class "Default")
      (node (ref "U3") (pin "91") (pinfunction "PD2/GTX0_91") (pintype "bidirectional"))
    )
    (net (code "84") (name "unconnected-(U3-PD3{slash}GTX1-Pad89)") (class "Default")
      (node (ref "U3") (pin "89") (pinfunction "PD3/GTX1_89") (pintype "bidirectional"))
    )
    (net (code "85") (name "unconnected-(U3-PD5{slash}GRX0-Pad87)") (class "Default")
      (node (ref "U3") (pin "87") (pinfunction "PD5/GRX0_87") (pintype "bidirectional"))
    )
    (net (code "86") (name "unconnected-(U3-PD6{slash}GRX1-Pad85)") (class "Default")
      (node (ref "U3") (pin "85") (pinfunction "PD6/GRX1_85") (pintype "bidirectional"))
    )
    (net (code "87") (name "unconnected-(U3-PD7{slash}GRXER-Pad84)") (class "Default")
      (node (ref "U3") (pin "84") (pinfunction "PD7/GRXER_84") (pintype "bidirectional"))
    )
    (net (code "88") (name "unconnected-(U3-PD8{slash}GMDC-Pad80)") (class "Default")
      (node (ref "U3") (pin "80") (pinfunction "PD8/GMDC_80") (pintype "bidirectional"))
    )
    (net (code "89") (name "unconnected-(U3-PD9{slash}GMDIO-Pad78)") (class "Default")
      (node (ref "U3") (pin "78") (pinfunction "PD9/GMDIO_78") (pintype "bidirectional"))
    )
    (net (code "90") (name "unconnected-(U3-PD10{slash}GCRS-Pad71)") (class "Default")
      (node (ref "U3") (pin "71") (pinfunction "PD10/GCRS_71") (pintype "bidirectional"))
    )
    (net (code "91") (name "unconnected-(U3-PD11{slash}GRX2-Pad69)") (class "Default")
      (node (ref "U3") (pin "69") (pinfunction "PD11/GRX2_69") (pintype "bidirectional"))
    )
    (net (code "92") (name "unconnected-(U3-PD12{slash}GRX3-Pad65)") (class "Default")
      (node (ref "U3") (pin "65") (pinfunction "PD12/GRX3_65") (pintype "bidirectional"))
    )
    (net (code "93") (name "unconnected-(U3-PD13{slash}GCOL-Pad62)") (class "Default")
      (node (ref "U3") (pin "62") (pinfunction "PD13/GCOL_62") (pintype "bidirectional"))
    )
    (net (code "94") (name "unconnected-(U3-PD14{slash}GRXCK-Pad59)") (class "Default")
      (node (ref "U3") (pin "59") (pinfunction "PD14/GRXCK_59") (pintype "bidirectional"))
    )
    (net (code "95") (name "unconnected-(U3-PD15{slash}GTX2-Pad75)") (class "Default")
      (node (ref "U3") (pin "75") (pinfunction "PD15/GTX2_75") (pintype "bidirectional"))
    )
    (net (code "96") (name "unconnected-(U3-PD16{slash}GTX3-Pad56)") (class "Default")
      (node (ref "U3") (pin "56") (pinfunction "PD16/GTX3_56") (pintype "bidirectional"))
    )
    (net (code "97") (name "unconnected-(U3-PD17{slash}GTXER-Pad53)") (class "Default")
      (node (ref "U3") (pin "53") (pinfunction "PD17/GTXER_53") (pintype "bidirectional"))
    )
    (net (code "98") (name "unconnected-(U3-PD18-Pad49)") (class "Default")
      (node (ref "U3") (pin "49") (pinfunction "PD18_49") (pintype "bidirectional"))
    )
    (net (code "99") (name "unconnected-(U3-PD20{slash}PWMH0-Pad45)") (class "Default")
      (node (ref "U3") (pin "45") (pinfunction "PD20/PWMH0_45") (pintype "bidirectional"))
    )
    (net (code "100") (name "unconnected-(U3-PD21{slash}PWMH1-Pad43)") (class "Default")
      (node (ref "U3") (pin "43") (pinfunction "PD21/PWMH1_43") (pintype "bidirectional"))
    )
    (net (code "101") (name "unconnected-(U3-PD22{slash}PWMH2-Pad41)") (class "Default")
      (node (ref "U3") (pin "41") (pinfunction "PD22/PWMH2_41") (pintype "bidirectional"))
    )
    (net (code "102") (name "unconnected-(U3-PD23{slash}PWMH3-Pad39)") (class "Default")
      (node (ref "U3") (pin "39") (pinfunction "PD23/PWMH3_39") (pintype "bidirectional"))
    )
    (net (code "103") (name "unconnected-(U3-PD24{slash}PWML0-Pad37)") (class "Default")
      (node (ref "U3") (pin "37") (pinfunction "PD24/PWML0_37") (pintype "bidirectional"))
    )
    (net (code "104") (name "unconnected-(U3-PD25{slash}PWML1-Pad35)") (class "Default")
      (node (ref "U3") (pin "35") (pinfunction "PD25/PWML1_35") (pintype "bidirectional"))
    )
    (net (code "105") (name "unconnected-(U3-PD26{slash}PWML2-Pad36)") (class "Default")
      (node (ref "U3") (pin "36") (pinfunction "PD26/PWML2_36") (pintype "bidirectional"))
    )
    (net (code "106") (name "unconnected-(U3-PD27{slash}PWML3-Pad32)") (class "Default")
      (node (ref "U3") (pin "32") (pinfunction "PD27/PWML3_32") (pintype "bidirectional"))
    )
    (net (code "107") (name "unconnected-(U3-PD28-Pad51)") (class "Default")
      (node (ref "U3") (pin "51") (pinfunction "PD28_51") (pintype "bidirectional"))
    )
    (net (code "108") (name "unconnected-(U3-PD29-Pad76)") (class "Default")
      (node (ref "U3") (pin "76") (pinfunction "PD29_76") (pintype "bidirectional"))
    )
    (net (code "109") (name "unconnected-(U3-PD31-Pad2)") (class "Default")
      (node (ref "U3") (pin "2") (pinfunction "PD31_2") (pintype "bidirectional"))
    )
    (net (code "110") (name "unconnected-(U3-TST-Pad60)") (class "Default")
      (node (ref "U3") (pin "60") (pinfunction "TST_60") (pintype "bidirectional"))
    )
  )
)
